# usb.net
KiCad netlist of a schematic drawn in EAGLE
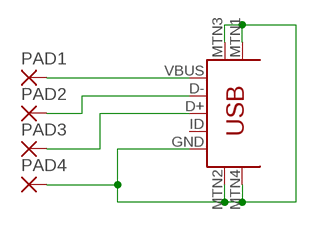
[diagram p0: schematic, sheet 1]

(export (version "E")
  (design (tool "Eeschema 10.0.6"))
  (components
    (comp (ref "PAD1")
      (value "SMD2")
      (footprint "eagle-import:SMD1,27-2,54")
      (libsource (lib "eagle-import") (part "SMD2"))
    )
    (comp (ref "PAD2")
      (value "SMD2")
      (footprint "eagle-import:SMD1,27-2,54")
      (libsource (lib "eagle-import") (part "SMD2"))
    )
    (comp (ref "PAD3")
      (value "SMD2")
      (footprint "eagle-import:SMD1,27-2,54")
      (libsource (lib "eagle-import") (part "SMD2"))
    )
    (comp (ref "PAD4")
      (value "SMD2")
      (footprint "eagle-import:SMD1,27-2,54")
      (libsource (lib "eagle-import") (part "SMD2"))
    )
    (comp (ref "USB1")
      (value "USB-MINIB-5PIN")
      (footprint "eagle-import:USB-MINIB")
      (libsource (lib "eagle-import") (part "USB-MINIB-5PIN"))
    )
  )
  (nets
    (net (code "1") (name "Net-(PAD1-P)") (class "Default")
      (node (ref "PAD1") (pin "1") (pinfunction "P_1") (pintype "passive"))
      (node (ref "USB1") (pin "VBUS") (pinfunction "VBUS_VBUS") (pintype "bidirectional"))
    )
    (net (code "2") (name "Net-(PAD2-P)") (class "Default")
      (node (ref "PAD2") (pin "1") (pinfunction "P_1") (pintype "passive"))
      (node (ref "USB1") (pin "D-") (pinfunction "D-_D-") (pintype "bidirectional"))
    )
    (net (code "3") (name "Net-(PAD3-P)") (class "Default")
      (node (ref "PAD3") (pin "1") (pinfunction "P_1") (pintype "passive"))
      (node (ref "USB1") (pin "D+") (pinfunction "D+_D+") (pintype "bidirectional"))
    )
    (net (code "4") (name "Net-(PAD4-P)") (class "Default")
      (node (ref "PAD4") (pin "1") (pinfunction "P_1") (pintype "passive"))
      (node (ref "USB1") (pin "GND") (pinfunction "GND_GND") (pintype "bidirectional"))
      (node (ref "USB1") (pin "MTN1") (pinfunction "MTN2_MTN1") (pintype "bidirectional"))
      (node (ref "USB1") (pin "MTN2") (pinfunction "MTN3_MTN2") (pintype "bidirectional"))
      (node (ref "USB1") (pin "MTN3") (pinfunction "MTN1_MTN3") (pintype "bidirectional"))
      (node (ref "USB1") (pin "MTN4") (pinfunction "MTN4_MTN4") (pintype "bidirectional"))
    )
    (net (code "5") (name "unconnected-(USB1-PadID)") (class "Default")
      (node (ref "USB1") (pin "ID") (pinfunction "ID_ID") (pintype "bidirectional"))
    )
  )
)
